# 3_DAC.net
KiCad netlist of a schematic drawn in Altium Designer
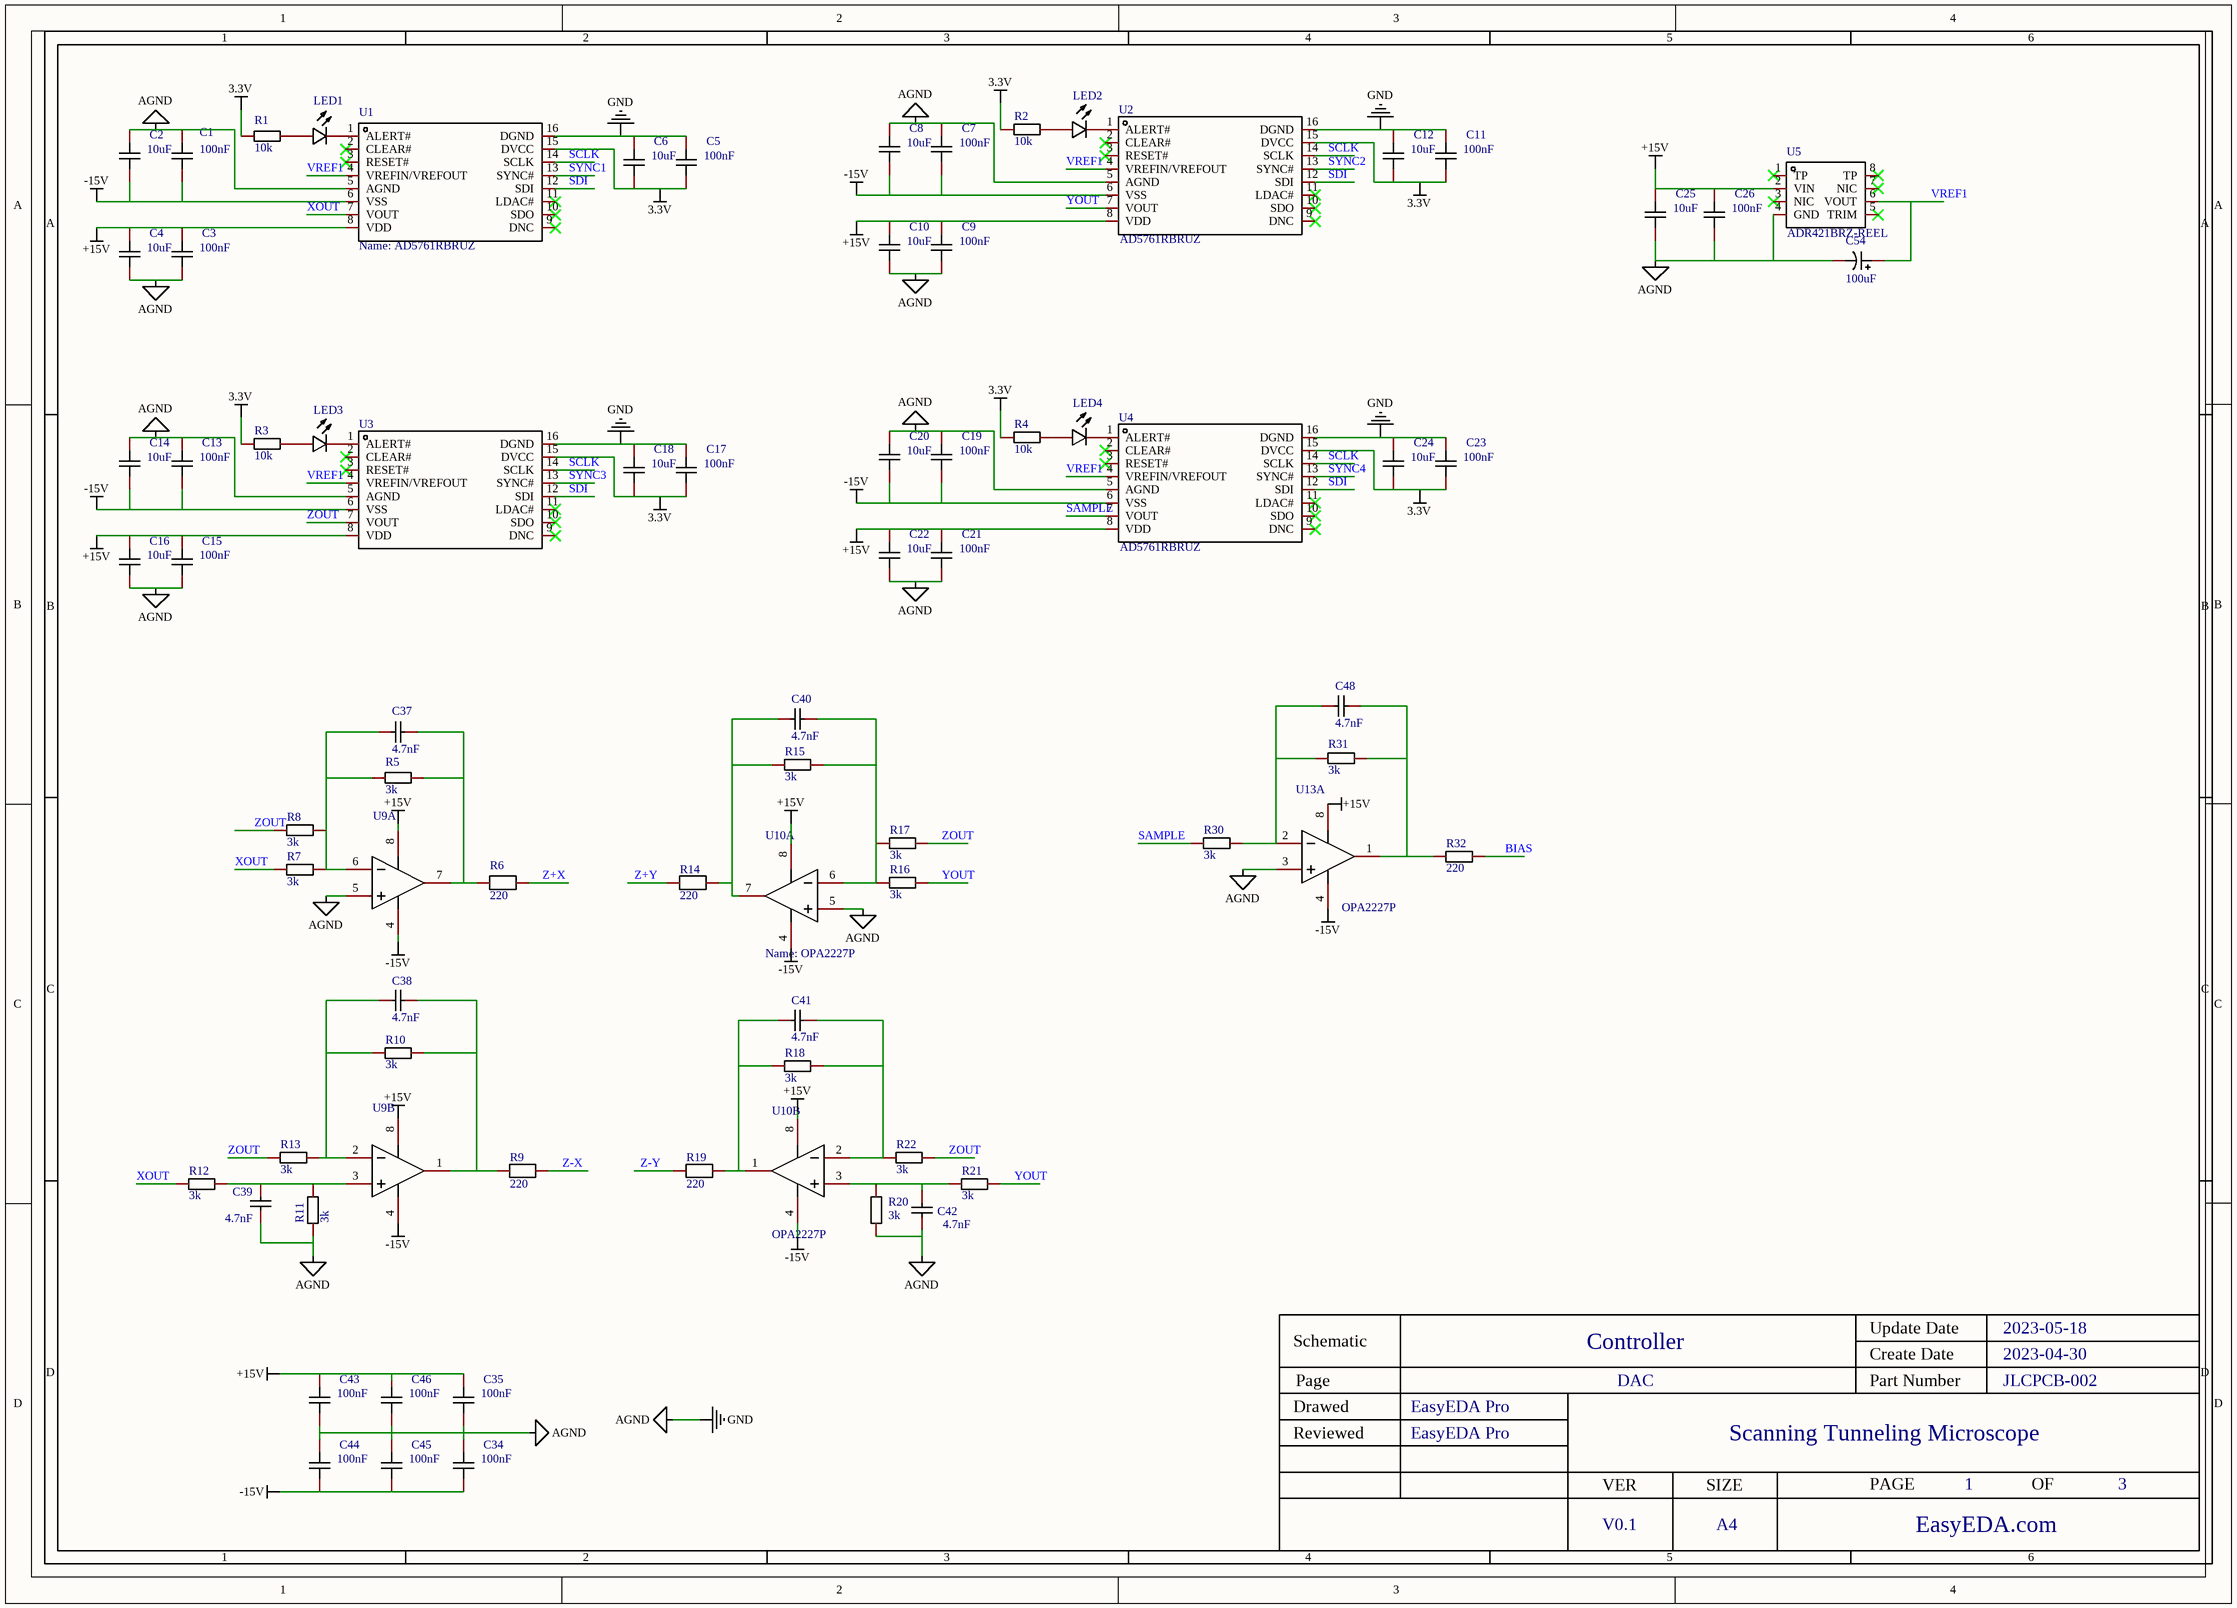
[diagram p0: 3_DAC.schdoc]

(export (version "E")
  (design (tool "Eeschema 10.0.6"))
  (components
    (comp (ref "C1")
      (value "100nF")
      (description "容值:100nF;精度:±10%;额定电压:25V;温度系数:X7R;")
      (fields
        (field (name "MANUFACTURER") "SAMSUNG(三星)")
        (field (name "MANUFACTURER PART") "CL10B104KA8NNNC")
      )
      (libsource (lib "altium-import") (part "root_1_CL10B104KA8NNNC_"))
    )
    (comp (ref "C2")
      (value "10uF")
      (description "容值:10uF;精度:±20%;额定电压:25V;温度系数:X5R;")
      (fields
        (field (name "MANUFACTURER") "muRata(村田)")
        (field (name "MANUFACTURER PART") "GRM188R61E106MA73D")
      )
      (libsource (lib "altium-import") (part "root_1_GRM188R61E106MA73D_"))
    )
    (comp (ref "C3")
      (value "100nF")
      (description "容值:100nF;精度:±10%;额定电压:25V;温度系数:X7R;")
      (fields
        (field (name "MANUFACTURER") "SAMSUNG(三星)")
        (field (name "MANUFACTURER PART") "CL10B104KA8NNNC")
      )
      (libsource (lib "altium-import") (part "root_1_CL10B104KA8NNNC_"))
    )
    (comp (ref "C4")
      (value "10uF")
      (description "容值:10uF;精度:±20%;额定电压:25V;温度系数:X5R;")
      (fields
        (field (name "MANUFACTURER") "muRata(村田)")
        (field (name "MANUFACTURER PART") "GRM188R61E106MA73D")
      )
      (libsource (lib "altium-import") (part "root_1_GRM188R61E106MA73D_"))
    )
    (comp (ref "C5")
      (value "100nF")
      (description "容值:100nF;精度:±10%;额定电压:25V;温度系数:X7R;")
      (fields
        (field (name "MANUFACTURER") "SAMSUNG(三星)")
        (field (name "MANUFACTURER PART") "CL10B104KA8NNNC")
      )
      (libsource (lib "altium-import") (part "root_1_CL10B104KA8NNNC_"))
    )
    (comp (ref "C6")
      (value "10uF")
      (description "容值:10uF;精度:±20%;额定电压:25V;温度系数:X5R;")
      (fields
        (field (name "MANUFACTURER") "muRata(村田)")
        (field (name "MANUFACTURER PART") "GRM188R61E106MA73D")
      )
      (libsource (lib "altium-import") (part "root_1_GRM188R61E106MA73D_"))
    )
    (comp (ref "C7")
      (value "100nF")
      (description "容值:100nF;精度:±10%;额定电压:25V;温度系数:X7R;")
      (fields
        (field (name "MANUFACTURER") "SAMSUNG(三星)")
        (field (name "MANUFACTURER PART") "CL10B104KA8NNNC")
      )
      (libsource (lib "altium-import") (part "root_1_CL10B104KA8NNNC_"))
    )
    (comp (ref "C8")
      (value "10uF")
      (description "容值:10uF;精度:±20%;额定电压:25V;温度系数:X5R;")
      (fields
        (field (name "MANUFACTURER") "muRata(村田)")
        (field (name "MANUFACTURER PART") "GRM188R61E106MA73D")
      )
      (libsource (lib "altium-import") (part "root_1_GRM188R61E106MA73D_"))
    )
    (comp (ref "C9")
      (value "100nF")
      (description "容值:100nF;精度:±10%;额定电压:25V;温度系数:X7R;")
      (fields
        (field (name "MANUFACTURER") "SAMSUNG(三星)")
        (field (name "MANUFACTURER PART") "CL10B104KA8NNNC")
      )
      (libsource (lib "altium-import") (part "root_1_CL10B104KA8NNNC_"))
    )
    (comp (ref "C10")
      (value "10uF")
      (description "容值:10uF;精度:±20%;额定电压:25V;温度系数:X5R;")
      (fields
        (field (name "MANUFACTURER") "muRata(村田)")
        (field (name "MANUFACTURER PART") "GRM188R61E106MA73D")
      )
      (libsource (lib "altium-import") (part "root_1_GRM188R61E106MA73D_"))
    )
    (comp (ref "C11")
      (value "100nF")
      (description "容值:100nF;精度:±10%;额定电压:25V;温度系数:X7R;")
      (fields
        (field (name "MANUFACTURER") "SAMSUNG(三星)")
        (field (name "MANUFACTURER PART") "CL10B104KA8NNNC")
      )
      (libsource (lib "altium-import") (part "root_1_CL10B104KA8NNNC_"))
    )
    (comp (ref "C12")
      (value "10uF")
      (description "容值:10uF;精度:±20%;额定电压:25V;温度系数:X5R;")
      (fields
        (field (name "MANUFACTURER") "muRata(村田)")
        (field (name "MANUFACTURER PART") "GRM188R61E106MA73D")
      )
      (libsource (lib "altium-import") (part "root_1_GRM188R61E106MA73D_"))
    )
    (comp (ref "C13")
      (value "100nF")
      (description "容值:100nF;精度:±10%;额定电压:25V;温度系数:X7R;")
      (fields
        (field (name "MANUFACTURER") "SAMSUNG(三星)")
        (field (name "MANUFACTURER PART") "CL10B104KA8NNNC")
      )
      (libsource (lib "altium-import") (part "root_1_CL10B104KA8NNNC_"))
    )
    (comp (ref "C14")
      (value "10uF")
      (description "容值:10uF;精度:±20%;额定电压:25V;温度系数:X5R;")
      (fields
        (field (name "MANUFACTURER") "muRata(村田)")
        (field (name "MANUFACTURER PART") "GRM188R61E106MA73D")
      )
      (libsource (lib "altium-import") (part "root_1_GRM188R61E106MA73D_"))
    )
    (comp (ref "C15")
      (value "100nF")
      (description "容值:100nF;精度:±10%;额定电压:25V;温度系数:X7R;")
      (fields
        (field (name "MANUFACTURER") "SAMSUNG(三星)")
        (field (name "MANUFACTURER PART") "CL10B104KA8NNNC")
      )
      (libsource (lib "altium-import") (part "root_1_CL10B104KA8NNNC_"))
    )
    (comp (ref "C16")
      (value "10uF")
      (description "容值:10uF;精度:±20%;额定电压:25V;温度系数:X5R;")
      (fields
        (field (name "MANUFACTURER") "muRata(村田)")
        (field (name "MANUFACTURER PART") "GRM188R61E106MA73D")
      )
      (libsource (lib "altium-import") (part "root_1_GRM188R61E106MA73D_"))
    )
    (comp (ref "C17")
      (value "100nF")
      (description "容值:100nF;精度:±10%;额定电压:25V;温度系数:X7R;")
      (fields
        (field (name "MANUFACTURER") "SAMSUNG(三星)")
        (field (name "MANUFACTURER PART") "CL10B104KA8NNNC")
      )
      (libsource (lib "altium-import") (part "root_1_CL10B104KA8NNNC_"))
    )
    (comp (ref "C18")
      (value "10uF")
      (description "容值:10uF;精度:±20%;额定电压:25V;温度系数:X5R;")
      (fields
        (field (name "MANUFACTURER") "muRata(村田)")
        (field (name "MANUFACTURER PART") "GRM188R61E106MA73D")
      )
      (libsource (lib "altium-import") (part "root_1_GRM188R61E106MA73D_"))
    )
    (comp (ref "C19")
      (value "100nF")
      (description "容值:100nF;精度:±10%;额定电压:25V;温度系数:X7R;")
      (fields
        (field (name "MANUFACTURER") "SAMSUNG(三星)")
        (field (name "MANUFACTURER PART") "CL10B104KA8NNNC")
      )
      (libsource (lib "altium-import") (part "root_1_CL10B104KA8NNNC_"))
    )
    (comp (ref "C20")
      (value "10uF")
      (description "容值:10uF;精度:±20%;额定电压:25V;温度系数:X5R;")
      (fields
        (field (name "MANUFACTURER") "muRata(村田)")
        (field (name "MANUFACTURER PART") "GRM188R61E106MA73D")
      )
      (libsource (lib "altium-import") (part "root_1_GRM188R61E106MA73D_"))
    )
    (comp (ref "C21")
      (value "100nF")
      (description "容值:100nF;精度:±10%;额定电压:25V;温度系数:X7R;")
      (fields
        (field (name "MANUFACTURER") "SAMSUNG(三星)")
        (field (name "MANUFACTURER PART") "CL10B104KA8NNNC")
      )
      (libsource (lib "altium-import") (part "root_1_CL10B104KA8NNNC_"))
    )
    (comp (ref "C22")
      (value "10uF")
      (description "容值:10uF;精度:±20%;额定电压:25V;温度系数:X5R;")
      (fields
        (field (name "MANUFACTURER") "muRata(村田)")
        (field (name "MANUFACTURER PART") "GRM188R61E106MA73D")
      )
      (libsource (lib "altium-import") (part "root_1_GRM188R61E106MA73D_"))
    )
    (comp (ref "C23")
      (value "100nF")
      (description "容值:100nF;精度:±10%;额定电压:25V;温度系数:X7R;")
      (fields
        (field (name "MANUFACTURER") "SAMSUNG(三星)")
        (field (name "MANUFACTURER PART") "CL10B104KA8NNNC")
      )
      (libsource (lib "altium-import") (part "root_1_CL10B104KA8NNNC_"))
    )
    (comp (ref "C24")
      (value "10uF")
      (description "容值:10uF;精度:±20%;额定电压:25V;温度系数:X5R;")
      (fields
        (field (name "MANUFACTURER") "muRata(村田)")
        (field (name "MANUFACTURER PART") "GRM188R61E106MA73D")
      )
      (libsource (lib "altium-import") (part "root_1_GRM188R61E106MA73D_"))
    )
    (comp (ref "C25")
      (value "10uF")
      (description "容值:10uF;精度:±20%;额定电压:25V;温度系数:X5R;")
      (fields
        (field (name "MANUFACTURER") "muRata(村田)")
        (field (name "MANUFACTURER PART") "GRM188R61E106MA73D")
      )
      (libsource (lib "altium-import") (part "root_1_GRM188R61E106MA73D_"))
    )
    (comp (ref "C26")
      (value "100nF")
      (description "容值:100nF;精度:±10%;额定电压:25V;温度系数:X7R;")
      (fields
        (field (name "MANUFACTURER") "SAMSUNG(三星)")
        (field (name "MANUFACTURER PART") "CL10B104KA8NNNC")
      )
      (libsource (lib "altium-import") (part "root_1_CL10B104KA8NNNC_"))
    )
    (comp (ref "C34")
      (value "100nF")
      (description "容值:100nF;精度:±10%;额定电压:25V;温度系数:X7R;")
      (fields
        (field (name "MANUFACTURER") "SAMSUNG(三星)")
        (field (name "MANUFACTURER PART") "CL10B104KA8NNNC")
      )
      (libsource (lib "altium-import") (part "root_1_CL10B104KA8NNNC_"))
    )
    (comp (ref "C35")
      (value "100nF")
      (description "容值:100nF;精度:±10%;额定电压:25V;温度系数:X7R;")
      (fields
        (field (name "MANUFACTURER") "SAMSUNG(三星)")
        (field (name "MANUFACTURER PART") "CL10B104KA8NNNC")
      )
      (libsource (lib "altium-import") (part "root_1_CL10B104KA8NNNC_"))
    )
    (comp (ref "C37")
      (value "4.7nF")
      (description "容值:4.7nF;精度:±10%;额定电压:50V;温度系数:X7R;")
      (fields (field (name "MANUFACTURER") "FH(风华)") (field (name "MANUFACTURER PART") "0603B472K500NT"))
      (libsource (lib "altium-import") (part "root_0_0603B472K500NT_"))
    )
    (comp (ref "C38")
      (value "4.7nF")
      (description "容值:4.7nF;精度:±10%;额定电压:50V;温度系数:X7R;")
      (fields (field (name "MANUFACTURER") "FH(风华)") (field (name "MANUFACTURER PART") "0603B472K500NT"))
      (libsource (lib "altium-import") (part "root_0_0603B472K500NT_"))
    )
    (comp (ref "C39")
      (value "4.7nF")
      (description "容值:4.7nF;精度:±10%;额定电压:50V;温度系数:X7R;")
      (fields (field (name "MANUFACTURER") "FH(风华)") (field (name "MANUFACTURER PART") "0603B472K500NT"))
      (libsource (lib "altium-import") (part "root_1_0603B472K500NT_"))
    )
    (comp (ref "C40")
      (value "4.7nF")
      (description "容值:4.7nF;精度:±10%;额定电压:50V;温度系数:X7R;")
      (fields (field (name "MANUFACTURER") "FH(风华)") (field (name "MANUFACTURER PART") "0603B472K500NT"))
      (libsource (lib "altium-import") (part "root_0_0603B472K500NT_"))
    )
    (comp (ref "C41")
      (value "4.7nF")
      (description "容值:4.7nF;精度:±10%;额定电压:50V;温度系数:X7R;")
      (fields (field (name "MANUFACTURER") "FH(风华)") (field (name "MANUFACTURER PART") "0603B472K500NT"))
      (libsource (lib "altium-import") (part "root_0_0603B472K500NT_"))
    )
    (comp (ref "C42")
      (value "4.7nF")
      (description "容值:4.7nF;精度:±10%;额定电压:50V;温度系数:X7R;")
      (fields (field (name "MANUFACTURER") "FH(风华)") (field (name "MANUFACTURER PART") "0603B472K500NT"))
      (libsource (lib "altium-import") (part "root_3_0603B472K500NT_"))
    )
    (comp (ref "C43")
      (value "100nF")
      (description "容值:100nF;精度:±10%;额定电压:25V;温度系数:X7R;")
      (fields
        (field (name "MANUFACTURER") "SAMSUNG(三星)")
        (field (name "MANUFACTURER PART") "CL10B104KA8NNNC")
      )
      (libsource (lib "altium-import") (part "root_1_CL10B104KA8NNNC_"))
    )
    (comp (ref "C44")
      (value "100nF")
      (description "容值:100nF;精度:±10%;额定电压:25V;温度系数:X7R;")
      (fields
        (field (name "MANUFACTURER") "SAMSUNG(三星)")
        (field (name "MANUFACTURER PART") "CL10B104KA8NNNC")
      )
      (libsource (lib "altium-import") (part "root_1_CL10B104KA8NNNC_"))
    )
    (comp (ref "C45")
      (value "100nF")
      (description "容值:100nF;精度:±10%;额定电压:25V;温度系数:X7R;")
      (fields
        (field (name "MANUFACTURER") "SAMSUNG(三星)")
        (field (name "MANUFACTURER PART") "CL10B104KA8NNNC")
      )
      (libsource (lib "altium-import") (part "root_1_CL10B104KA8NNNC_"))
    )
    (comp (ref "C46")
      (value "100nF")
      (description "容值:100nF;精度:±10%;额定电压:25V;温度系数:X7R;")
      (fields
        (field (name "MANUFACTURER") "SAMSUNG(三星)")
        (field (name "MANUFACTURER PART") "CL10B104KA8NNNC")
      )
      (libsource (lib "altium-import") (part "root_1_CL10B104KA8NNNC_"))
    )
    (comp (ref "C48")
      (value "4.7nF")
      (description "容值:4.7nF;精度:±10%;额定电压:50V;温度系数:X7R;")
      (fields (field (name "MANUFACTURER") "FH(风华)") (field (name "MANUFACTURER PART") "0603B472K500NT"))
      (libsource (lib "altium-import") (part "root_0_0603B472K500NT_"))
    )
    (comp (ref "C54")
      (value "100uF")
      (fields
        (field (name "NAME") "100uF")
        (field (name "MANUFACTURER") "Kyocera AVX")
        (field (name "MANUFACTURER PART") "F931D107MNC")
        (field (name "TOLERANCE") "±20%")
      )
      (libsource (lib "altium-import") (part "root_2_F931D107MNC_"))
    )
    (comp (ref "LED1")
      (value "19-217/R6C-AL1M2VY/3T")
      (fields (field (name "MANUFACTURER") "EVERLIGHT(台湾亿光)"))
      (libsource (lib "altium-import") (part "root_0_19-217/R6C-AL1M2VY/3T_"))
    )
    (comp (ref "LED2")
      (value "19-217/R6C-AL1M2VY/3T")
      (fields (field (name "MANUFACTURER") "EVERLIGHT(台湾亿光)"))
      (libsource (lib "altium-import") (part "root_0_19-217/R6C-AL1M2VY/3T_"))
    )
    (comp (ref "LED3")
      (value "19-217/R6C-AL1M2VY/3T")
      (fields (field (name "MANUFACTURER") "EVERLIGHT(台湾亿光)"))
      (libsource (lib "altium-import") (part "root_0_19-217/R6C-AL1M2VY/3T_"))
    )
    (comp (ref "LED4")
      (value "19-217/R6C-AL1M2VY/3T")
      (fields (field (name "MANUFACTURER") "EVERLIGHT(台湾亿光)"))
      (libsource (lib "altium-import") (part "root_0_19-217/R6C-AL1M2VY/3T_"))
    )
    (comp (ref "R1")
      (value "10k")
      (description "电阻类型:厚膜电阻;阻值:10k;精度:±1%;功率:1/10W;温度系数:±100ppm/;最大工作电压:75V;工作温度范围:-55~+155;")
      (fields
        (field (name "MANUFACTURER") "UNI-ROYAL(厚声)")
        (field (name "MANUFACTURER PART") "0603WAF1002T5E")
      )
      (libsource (lib "altium-import") (part "root_0_0603WAF1002T5E_"))
    )
    (comp (ref "R2")
      (value "10k")
      (description "电阻类型:厚膜电阻;阻值:10k;精度:±1%;功率:1/10W;温度系数:±100ppm/;最大工作电压:75V;工作温度范围:-55~+155;")
      (fields
        (field (name "MANUFACTURER") "UNI-ROYAL(厚声)")
        (field (name "MANUFACTURER PART") "0603WAF1002T5E")
      )
      (libsource (lib "altium-import") (part "root_0_0603WAF1002T5E_"))
    )
    (comp (ref "R3")
      (value "10k")
      (description "电阻类型:厚膜电阻;阻值:10k;精度:±1%;功率:1/10W;温度系数:±100ppm/;最大工作电压:75V;工作温度范围:-55~+155;")
      (fields
        (field (name "MANUFACTURER") "UNI-ROYAL(厚声)")
        (field (name "MANUFACTURER PART") "0603WAF1002T5E")
      )
      (libsource (lib "altium-import") (part "root_0_0603WAF1002T5E_"))
    )
    (comp (ref "R4")
      (value "10k")
      (description "电阻类型:厚膜电阻;阻值:10k;精度:±1%;功率:1/10W;温度系数:±100ppm/;最大工作电压:75V;工作温度范围:-55~+155;")
      (fields
        (field (name "MANUFACTURER") "UNI-ROYAL(厚声)")
        (field (name "MANUFACTURER PART") "0603WAF1002T5E")
      )
      (libsource (lib "altium-import") (part "root_0_0603WAF1002T5E_"))
    )
    (comp (ref "R5")
      (value "3k")
      (description "电阻类型:薄膜电阻;阻值:3k;精度:±0.5%;功率:100mW;温度系数:±25ppm/;最大工作电压:75V;工作温度范围:-55~+155;")
      (fields (field (name "MANUFACTURER") "光颉(Viking)") (field (name "MANUFACTURER PART") "ARG03DTC3001"))
      (libsource (lib "altium-import") (part "root_0_ARG03DTC3001_"))
    )
    (comp (ref "R6")
      (value "220")
      (description "阻值:220;精度:±0.5%;功率:100mW;温度系数:±50ppm/;最大工作电压:-;工作温度范围:-55~+155;")
      (fields (field (name "MANUFACTURER") "PANASONIC(松下)") (field (name "MANUFACTURER PART") "ERJU3RD2200V"))
      (libsource (lib "altium-import") (part "root_0_ERJU3RD2200V_"))
    )
    (comp (ref "R7")
      (value "3k")
      (description "电阻类型:薄膜电阻;阻值:3k;精度:±0.5%;功率:100mW;温度系数:±25ppm/;最大工作电压:75V;工作温度范围:-55~+155;")
      (fields (field (name "MANUFACTURER") "光颉(Viking)") (field (name "MANUFACTURER PART") "ARG03DTC3001"))
      (libsource (lib "altium-import") (part "root_0_ARG03DTC3001_"))
    )
    (comp (ref "R8")
      (value "3k")
      (description "电阻类型:薄膜电阻;阻值:3k;精度:±0.5%;功率:100mW;温度系数:±25ppm/;最大工作电压:75V;工作温度范围:-55~+155;")
      (fields (field (name "MANUFACTURER") "光颉(Viking)") (field (name "MANUFACTURER PART") "ARG03DTC3001"))
      (libsource (lib "altium-import") (part "root_0_ARG03DTC3001_"))
    )
    (comp (ref "R9")
      (value "220")
      (description "阻值:220;精度:±0.5%;功率:100mW;温度系数:±50ppm/;最大工作电压:-;工作温度范围:-55~+155;")
      (fields (field (name "MANUFACTURER") "PANASONIC(松下)") (field (name "MANUFACTURER PART") "ERJU3RD2200V"))
      (libsource (lib "altium-import") (part "root_0_ERJU3RD2200V_"))
    )
    (comp (ref "R10")
      (value "3k")
      (description "电阻类型:薄膜电阻;阻值:3k;精度:±0.5%;功率:100mW;温度系数:±25ppm/;最大工作电压:75V;工作温度范围:-55~+155;")
      (fields (field (name "MANUFACTURER") "光颉(Viking)") (field (name "MANUFACTURER PART") "ARG03DTC3001"))
      (libsource (lib "altium-import") (part "root_0_ARG03DTC3001_"))
    )
    (comp (ref "R11")
      (value "3k")
      (description "电阻类型:薄膜电阻;阻值:3k;精度:±0.5%;功率:100mW;温度系数:±25ppm/;最大工作电压:75V;工作温度范围:-55~+155;")
      (fields (field (name "MANUFACTURER") "光颉(Viking)") (field (name "MANUFACTURER PART") "ARG03DTC3001"))
      (libsource (lib "altium-import") (part "root_1_ARG03DTC3001_"))
    )
    (comp (ref "R12")
      (value "3k")
      (description "电阻类型:薄膜电阻;阻值:3k;精度:±0.5%;功率:100mW;温度系数:±25ppm/;最大工作电压:75V;工作温度范围:-55~+155;")
      (fields (field (name "MANUFACTURER") "光颉(Viking)") (field (name "MANUFACTURER PART") "ARG03DTC3001"))
      (libsource (lib "altium-import") (part "root_0_ARG03DTC3001_"))
    )
    (comp (ref "R13")
      (value "3k")
      (description "电阻类型:薄膜电阻;阻值:3k;精度:±0.5%;功率:100mW;温度系数:±25ppm/;最大工作电压:75V;工作温度范围:-55~+155;")
      (fields (field (name "MANUFACTURER") "光颉(Viking)") (field (name "MANUFACTURER PART") "ARG03DTC3001"))
      (libsource (lib "altium-import") (part "root_0_ARG03DTC3001_"))
    )
    (comp (ref "R14")
      (value "220")
      (description "阻值:220;精度:±0.5%;功率:100mW;温度系数:±50ppm/;最大工作电压:-;工作温度范围:-55~+155;")
      (fields (field (name "MANUFACTURER") "PANASONIC(松下)") (field (name "MANUFACTURER PART") "ERJU3RD2200V"))
      (libsource (lib "altium-import") (part "root_0_ERJU3RD2200V_"))
    )
    (comp (ref "R15")
      (value "3k")
      (description "电阻类型:薄膜电阻;阻值:3k;精度:±0.5%;功率:100mW;温度系数:±25ppm/;最大工作电压:75V;工作温度范围:-55~+155;")
      (fields (field (name "MANUFACTURER") "光颉(Viking)") (field (name "MANUFACTURER PART") "ARG03DTC3001"))
      (libsource (lib "altium-import") (part "root_0_ARG03DTC3001_"))
    )
    (comp (ref "R16")
      (value "3k")
      (description "电阻类型:薄膜电阻;阻值:3k;精度:±0.5%;功率:100mW;温度系数:±25ppm/;最大工作电压:75V;工作温度范围:-55~+155;")
      (fields (field (name "MANUFACTURER") "光颉(Viking)") (field (name "MANUFACTURER PART") "ARG03DTC3001"))
      (libsource (lib "altium-import") (part "root_0_ARG03DTC3001_"))
    )
    (comp (ref "R17")
      (value "3k")
      (description "电阻类型:薄膜电阻;阻值:3k;精度:±0.5%;功率:100mW;温度系数:±25ppm/;最大工作电压:75V;工作温度范围:-55~+155;")
      (fields (field (name "MANUFACTURER") "光颉(Viking)") (field (name "MANUFACTURER PART") "ARG03DTC3001"))
      (libsource (lib "altium-import") (part "root_0_ARG03DTC3001_"))
    )
    (comp (ref "R18")
      (value "3k")
      (description "电阻类型:薄膜电阻;阻值:3k;精度:±0.5%;功率:100mW;温度系数:±25ppm/;最大工作电压:75V;工作温度范围:-55~+155;")
      (fields (field (name "MANUFACTURER") "光颉(Viking)") (field (name "MANUFACTURER PART") "ARG03DTC3001"))
      (libsource (lib "altium-import") (part "root_0_ARG03DTC3001_"))
    )
    (comp (ref "R19")
      (value "220")
      (description "阻值:220;精度:±0.5%;功率:100mW;温度系数:±50ppm/;最大工作电压:-;工作温度范围:-55~+155;")
      (fields (field (name "MANUFACTURER") "PANASONIC(松下)") (field (name "MANUFACTURER PART") "ERJU3RD2200V"))
      (libsource (lib "altium-import") (part "root_0_ERJU3RD2200V_"))
    )
    (comp (ref "R20")
      (value "3k")
      (description "电阻类型:薄膜电阻;阻值:3k;精度:±0.5%;功率:100mW;温度系数:±25ppm/;最大工作电压:75V;工作温度范围:-55~+155;")
      (fields (field (name "MANUFACTURER") "光颉(Viking)") (field (name "MANUFACTURER PART") "ARG03DTC3001"))
      (libsource (lib "altium-import") (part "root_3_ARG03DTC3001_"))
    )
    (comp (ref "R21")
      (value "3k")
      (description "电阻类型:薄膜电阻;阻值:3k;精度:±0.5%;功率:100mW;温度系数:±25ppm/;最大工作电压:75V;工作温度范围:-55~+155;")
      (fields (field (name "MANUFACTURER") "光颉(Viking)") (field (name "MANUFACTURER PART") "ARG03DTC3001"))
      (libsource (lib "altium-import") (part "root_0_ARG03DTC3001_"))
    )
    (comp (ref "R22")
      (value "3k")
      (description "电阻类型:薄膜电阻;阻值:3k;精度:±0.5%;功率:100mW;温度系数:±25ppm/;最大工作电压:75V;工作温度范围:-55~+155;")
      (fields (field (name "MANUFACTURER") "光颉(Viking)") (field (name "MANUFACTURER PART") "ARG03DTC3001"))
      (libsource (lib "altium-import") (part "root_0_ARG03DTC3001_"))
    )
    (comp (ref "R30")
      (value "3k")
      (description "电阻类型:薄膜电阻;阻值:3k;精度:±0.5%;功率:100mW;温度系数:±25ppm/;最大工作电压:75V;工作温度范围:-55~+155;")
      (fields (field (name "MANUFACTURER") "光颉(Viking)") (field (name "MANUFACTURER PART") "ARG03DTC3001"))
      (libsource (lib "altium-import") (part "root_0_ARG03DTC3001_"))
    )
    (comp (ref "R31")
      (value "3k")
      (description "电阻类型:薄膜电阻;阻值:3k;精度:±0.5%;功率:100mW;温度系数:±25ppm/;最大工作电压:75V;工作温度范围:-55~+155;")
      (fields (field (name "MANUFACTURER") "光颉(Viking)") (field (name "MANUFACTURER PART") "ARG03DTC3001"))
      (libsource (lib "altium-import") (part "root_0_ARG03DTC3001_"))
    )
    (comp (ref "R32")
      (value "220")
      (description "电阻类型:薄膜电阻;阻值:3k;精度:±0.5%;功率:100mW;温度系数:±25ppm/;最大工作电压:75V;工作温度范围:-55~+155;")
      (fields (field (name "MANUFACTURER") "光颉(Viking)") (field (name "MANUFACTURER PART") "ARG03DTC3001"))
      (libsource (lib "altium-import") (part "root_0_ARG03DTC3001_"))
    )
    (comp (ref "U1")
      (value "AD5761RBRUZ")
      (description "D/A 位数:-;D/A通道数:-;输出类型:-;读写接口类型:-;")
      (fields (field (name "NAME") "AD5761RBRUZ") (field (name "MANUFACTURER") "ADI(亚德诺)/LINEAR"))
      (libsource (lib "altium-import") (part "root_0_AD5761RBRUZ_"))
    )
    (comp (ref "U2")
      (value "AD5761RBRUZ")
      (description "D/A 位数:-;D/A通道数:-;输出类型:-;读写接口类型:-;")
      (fields (field (name "NAME") "AD5761RBRUZ") (field (name "MANUFACTURER") "ADI(亚德诺)/LINEAR"))
      (libsource (lib "altium-import") (part "root_0_AD5761RBRUZ_"))
    )
    (comp (ref "U3")
      (value "AD5761RBRUZ")
      (description "D/A 位数:-;D/A通道数:-;输出类型:-;读写接口类型:-;")
      (fields (field (name "MANUFACTURER") "ADI(亚德诺)/LINEAR"))
      (libsource (lib "altium-import") (part "root_0_AD5761RBRUZ_"))
    )
    (comp (ref "U4")
      (value "AD5761RBRUZ")
      (description "D/A 位数:-;D/A通道数:-;输出类型:-;读写接口类型:-;")
      (fields (field (name "NAME") "AD5761RBRUZ") (field (name "MANUFACTURER") "ADI(亚德诺)/LINEAR"))
      (libsource (lib "altium-import") (part "root_0_AD5761RBRUZ_"))
    )
    (comp (ref "U5")
      (value "ADR421BRZ-REEL")
      (fields (field (name "NAME") "ADR421BRZ-REEL") (field (name "MANUFACTURER") "ADI(亚德诺)/LINEAR"))
      (libsource (lib "altium-import") (part "root_0_ADR421BRZ-REEL_"))
    )
    (comp (ref "U9")
      (value "OPA2227P")
      (fields (field (name "MANUFACTURER") "TI(德州仪器)"))
      (libsource (lib "altium-import") (part "root_0_OPA2227P_"))
    )
    (comp (ref "U10")
      (value "OPA2227P")
      (fields (field (name "NAME") "OPA2227P") (field (name "MANUFACTURER") "TI(德州仪器)"))
      (libsource (lib "altium-import") (part "root_0_mirrored_OPA2227P_"))
    )
    (comp (ref "U13")
      (value "OPA2227P")
      (fields (field (name "NAME") "OPA2227P") (field (name "MANUFACTURER") "TI(德州仪器)"))
      (libsource (lib "") (part "root_0_OPA2227P__1"))
    )
  )
  (nets
    (net (code "1") (name "+15V") (class "Default")
      (node (ref "C10") (pin "2") (pinfunction "2_2") (pintype "passive"))
      (node (ref "C15") (pin "2") (pinfunction "2_2") (pintype "passive"))
      (node (ref "C16") (pin "2") (pinfunction "2_2") (pintype "passive"))
      (node (ref "C21") (pin "2") (pinfunction "2_2") (pintype "passive"))
      (node (ref "C22") (pin "2") (pinfunction "2_2") (pintype "passive"))
      (node (ref "C25") (pin "2") (pinfunction "2_2") (pintype "passive"))
      (node (ref "C26") (pin "2") (pinfunction "2_2") (pintype "passive"))
      (node (ref "C3") (pin "2") (pinfunction "2_2") (pintype "passive"))
      (node (ref "C35") (pin "2") (pinfunction "2_2") (pintype "passive"))
      (node (ref "C4") (pin "2") (pinfunction "2_2") (pintype "passive"))
      (node (ref "C43") (pin "2") (pinfunction "2_2") (pintype "passive"))
      (node (ref "C46") (pin "2") (pinfunction "2_2") (pintype "passive"))
      (node (ref "C9") (pin "2") (pinfunction "2_2") (pintype "passive"))
      (node (ref "U1") (pin "8") (pinfunction "VDD_8") (pintype "passive"))
      (node (ref "U10") (pin "8") (pinfunction "V+_8") (pintype "passive"))
      (node (ref "U13") (pin "8") (pinfunction "V+_8") (pintype "passive"))
      (node (ref "U2") (pin "8") (pinfunction "VDD_8") (pintype "passive"))
      (node (ref "U3") (pin "8") (pinfunction "VDD_8") (pintype "passive"))
      (node (ref "U4") (pin "8") (pinfunction "VDD_8") (pintype "passive"))
      (node (ref "U5") (pin "2") (pinfunction "VIN_2") (pintype "passive"))
      (node (ref "U9") (pin "8") (pinfunction "V+_8") (pintype "passive"))
    )
    (net (code "2") (name "-15V") (class "Default")
      (node (ref "C1") (pin "1") (pinfunction "1_1") (pintype "passive"))
      (node (ref "C13") (pin "1") (pinfunction "1_1") (pintype "passive"))
      (node (ref "C14") (pin "1") (pinfunction "1_1") (pintype "passive"))
      (node (ref "C19") (pin "1") (pinfunction "1_1") (pintype "passive"))
      (node (ref "C2") (pin "1") (pinfunction "1_1") (pintype "passive"))
      (node (ref "C20") (pin "1") (pinfunction "1_1") (pintype "passive"))
      (node (ref "C34") (pin "1") (pinfunction "1_1") (pintype "passive"))
      (node (ref "C44") (pin "1") (pinfunction "1_1") (pintype "passive"))
      (node (ref "C45") (pin "1") (pinfunction "1_1") (pintype "passive"))
      (node (ref "C7") (pin "1") (pinfunction "1_1") (pintype "passive"))
      (node (ref "C8") (pin "1") (pinfunction "1_1") (pintype "passive"))
      (node (ref "U1") (pin "6") (pinfunction "VSS_6") (pintype "passive"))
      (node (ref "U10") (pin "4") (pinfunction "V-_4") (pintype "passive"))
      (node (ref "U13") (pin "4") (pinfunction "V-_4") (pintype "passive"))
      (node (ref "U2") (pin "6") (pinfunction "VSS_6") (pintype "passive"))
      (node (ref "U3") (pin "6") (pinfunction "VSS_6") (pintype "passive"))
      (node (ref "U4") (pin "6") (pinfunction "VSS_6") (pintype "passive"))
      (node (ref "U9") (pin "4") (pinfunction "V-_4") (pintype "passive"))
    )
    (net (code "3") (name "/BIAS") (class "Default")
      (node (ref "R32") (pin "2") (pinfunction "2_2") (pintype "passive"))
    )
    (net (code "4") (name "/SAMPLE") (class "Default")
      (node (ref "R30") (pin "1") (pinfunction "1_1") (pintype "passive"))
      (node (ref "U4") (pin "7") (pinfunction "VOUT_7") (pintype "passive"))
    )
    (net (code "5") (name "/SCLK") (class "Default")
      (node (ref "U1") (pin "14") (pinfunction "SCLK_14") (pintype "passive"))
      (node (ref "U2") (pin "14") (pinfunction "SCLK_14") (pintype "passive"))
      (node (ref "U3") (pin "14") (pinfunction "SCLK_14") (pintype "passive"))
      (node (ref "U4") (pin "14") (pinfunction "SCLK_14") (pintype "passive"))
    )
    (net (code "6") (name "/SDI") (class "Default")
      (node (ref "U1") (pin "12") (pinfunction "SDI_12") (pintype "passive"))
      (node (ref "U2") (pin "12") (pinfunction "SDI_12") (pintype "passive"))
      (node (ref "U3") (pin "12") (pinfunction "SDI_12") (pintype "passive"))
      (node (ref "U4") (pin "12") (pinfunction "SDI_12") (pintype "passive"))
    )
    (net (code "7") (name "/SYNC1") (class "Default")
      (node (ref "U1") (pin "13") (pinfunction "SYNC#_13") (pintype "passive"))
    )
    (net (code "8") (name "/SYNC2") (class "Default")
      (node (ref "U2") (pin "13") (pinfunction "SYNC#_13") (pintype "passive"))
    )
    (net (code "9") (name "/SYNC3") (class "Default")
      (node (ref "U3") (pin "13") (pinfunction "SYNC#_13") (pintype "passive"))
    )
    (net (code "10") (name "/SYNC4") (class "Default")
      (node (ref "U4") (pin "13") (pinfunction "SYNC#_13") (pintype "passive"))
    )
    (net (code "11") (name "/VREF1") (class "Default")
      (node (ref "C54") (pin "1") (pinfunction "1_1") (pintype "passive"))
      (node (ref "U1") (pin "4") (pinfunction "VREFIN/VREFOUT_4") (pintype "passive"))
      (node (ref "U2") (pin "4") (pinfunction "VREFIN/VREFOUT_4") (pintype "passive"))
      (node (ref "U3") (pin "4") (pinfunction "VREFIN/VREFOUT_4") (pintype "passive"))
      (node (ref "U4") (pin "4") (pinfunction "VREFIN/VREFOUT_4") (pintype "passive"))
      (node (ref "U5") (pin "6") (pinfunction "VOUT_6") (pintype "passive"))
    )
    (net (code "12") (name "/XOUT") (class "Default")
      (node (ref "R12") (pin "1") (pinfunction "1_1") (pintype "passive"))
      (node (ref "R7") (pin "1") (pinfunction "1_1") (pintype "passive"))
      (node (ref "U1") (pin "7") (pinfunction "VOUT_7") (pintype "passive"))
    )
    (net (code "13") (name "/YOUT") (class "Default")
      (node (ref "R16") (pin "2") (pinfunction "2_2") (pintype "passive"))
      (node (ref "R21") (pin "2") (pinfunction "2_2") (pintype "passive"))
      (node (ref "U2") (pin "7") (pinfunction "VOUT_7") (pintype "passive"))
    )
    (net (code "14") (name "/Z+X") (class "Default")
      (node (ref "R6") (pin "2") (pinfunction "2_2") (pintype "passive"))
    )
    (net (code "15") (name "/Z+Y") (class "Default")
      (node (ref "R14") (pin "1") (pinfunction "1_1") (pintype "passive"))
    )
    (net (code "16") (name "/Z-X") (class "Default")
      (node (ref "R9") (pin "2") (pinfunction "2_2") (pintype "passive"))
    )
    (net (code "17") (name "/Z-Y") (class "Default")
      (node (ref "R19") (pin "1") (pinfunction "1_1") (pintype "passive"))
    )
    (net (code "18") (name "/ZOUT") (class "Default")
      (node (ref "R13") (pin "1") (pinfunction "1_1") (pintype "passive"))
      (node (ref "R17") (pin "2") (pinfunction "2_2") (pintype "passive"))
      (node (ref "R22") (pin "2") (pinfunction "2_2") (pintype "passive"))
      (node (ref "R8") (pin "1") (pinfunction "1_1") (pintype "passive"))
      (node (ref "U3") (pin "7") (pinfunction "VOUT_7") (pintype "passive"))
    )
    (net (code "19") (name "3.3V") (class "Default")
      (node (ref "C11") (pin "1") (pinfunction "1_1") (pintype "passive"))
      (node (ref "C12") (pin "1") (pinfunction "1_1") (pintype "passive"))
      (node (ref "C17") (pin "1") (pinfunction "1_1") (pintype "passive"))
      (node (ref "C18") (pin "1") (pinfunction "1_1") (pintype "passive"))
      (node (ref "C23") (pin "1") (pinfunction "1_1") (pintype "passive"))
      (node (ref "C24") (pin "1") (pinfunction "1_1") (pintype "passive"))
      (node (ref "C5") (pin "1") (pinfunction "1_1") (pintype "passive"))
      (node (ref "C6") (pin "1") (pinfunction "1_1") (pintype "passive"))
      (node (ref "R1") (pin "1") (pinfunction "1_1") (pintype "passive"))
      (node (ref "R2") (pin "1") (pinfunction "1_1") (pintype "passive"))
      (node (ref "R3") (pin "1") (pinfunction "1_1") (pintype "passive"))
      (node (ref "R4") (pin "1") (pinfunction "1_1") (pintype "passive"))
      (node (ref "U1") (pin "15") (pinfunction "DVCC_15") (pintype "passive"))
      (node (ref "U2") (pin "15") (pinfunction "DVCC_15") (pintype "passive"))
      (node (ref "U3") (pin "15") (pinfunction "DVCC_15") (pintype "passive"))
      (node (ref "U4") (pin "15") (pinfunction "DVCC_15") (pintype "passive"))
    )
    (net (code "20") (name "AGND") (class "Default")
      (node (ref "C1") (pin "2") (pinfunction "2_2") (pintype "passive"))
      (node (ref "C10") (pin "1") (pinfunction "1_1") (pintype "passive"))
      (node (ref "C11") (pin "2") (pinfunction "2_2") (pintype "passive"))
      (node (ref "C12") (pin "2") (pinfunction "2_2") (pintype "passive"))
      (node (ref "C13") (pin "2") (pinfunction "2_2") (pintype "passive"))
      (node (ref "C14") (pin "2") (pinfunction "2_2") (pintype "passive"))
      (node (ref "C15") (pin "1") (pinfunction "1_1") (pintype "passive"))
      (node (ref "C16") (pin "1") (pinfunction "1_1") (pintype "passive"))
      (node (ref "C17") (pin "2") (pinfunction "2_2") (pintype "passive"))
      (node (ref "C18") (pin "2") (pinfunction "2_2") (pintype "passive"))
      (node (ref "C19") (pin "2") (pinfunction "2_2") (pintype "passive"))
      (node (ref "C2") (pin "2") (pinfunction "2_2") (pintype "passive"))
      (node (ref "C20") (pin "2") (pinfunction "2_2") (pintype "passive"))
      (node (ref "C21") (pin "1") (pinfunction "1_1") (pintype "passive"))
      (node (ref "C22") (pin "1") (pinfunction "1_1") (pintype "passive"))
      (node (ref "C23") (pin "2") (pinfunction "2_2") (pintype "passive"))
      (node (ref "C24") (pin "2") (pinfunction "2_2") (pintype "passive"))
      (node (ref "C25") (pin "1") (pinfunction "1_1") (pintype "passive"))
      (node (ref "C26") (pin "1") (pinfunction "1_1") (pintype "passive"))
      (node (ref "C3") (pin "1") (pinfunction "1_1") (pintype "passive"))
      (node (ref "C34") (pin "2") (pinfunction "2_2") (pintype "passive"))
      (node (ref "C35") (pin "1") (pinfunction "1_1") (pintype "passive"))
      (node (ref "C39") (pin "1") (pinfunction "1_1") (pintype "passive"))
      (node (ref "C4") (pin "1") (pinfunction "1_1") (pintype "passive"))
      (node (ref "C42") (pin "2") (pinfunction "2_2") (pintype "passive"))
      (node (ref "C43") (pin "1") (pinfunction "1_1") (pintype "passive"))
      (node (ref "C44") (pin "2") (pinfunction "2_2") (pintype "passive"))
      (node (ref "C45") (pin "2") (pinfunction "2_2") (pintype "passive"))
      (node (ref "C46") (pin "1") (pinfunction "1_1") (pintype "passive"))
      (node (ref "C5") (pin "2") (pinfunction "2_2") (pintype "passive"))
      (node (ref "C54") (pin "2") (pinfunction "2_2") (pintype "passive"))
      (node (ref "C6") (pin "2") (pinfunction "2_2") (pintype "passive"))
      (node (ref "C7") (pin "2") (pinfunction "2_2") (pintype "passive"))
      (node (ref "C8") (pin "2") (pinfunction "2_2") (pintype "passive"))
      (node (ref "C9") (pin "1") (pinfunction "1_1") (pintype "passive"))
      (node (ref "R11") (pin "1") (pinfunction "1_1") (pintype "passive"))
      (node (ref "R20") (pin "2") (pinfunction "2_2") (pintype "passive"))
      (node (ref "U1") (pin "16") (pinfunction "DGND_16") (pintype "passive"))
      (node (ref "U1") (pin "5") (pinfunction "AGND_5") (pintype "passive"))
      (node (ref "U10") (pin "5") (pinfunction "IN_B+_5") (pintype "passive"))
      (node (ref "U13") (pin "3") (pinfunction "INA+_3") (pintype "passive"))
      (node (ref "U2") (pin "16") (pinfunction "DGND_16") (pintype "passive"))
      (node (ref "U2") (pin "5") (pinfunction "AGND_5") (pintype "passive"))
      (node (ref "U3") (pin "16") (pinfunction "DGND_16") (pintype "passive"))
      (node (ref "U3") (pin "5") (pinfunction "AGND_5") (pintype "passive"))
      (node (ref "U4") (pin "16") (pinfunction "DGND_16") (pintype "passive"))
      (node (ref "U4") (pin "5") (pinfunction "AGND_5") (pintype "passive"))
      (node (ref "U5") (pin "4") (pinfunction "GND_4") (pintype "passive"))
      (node (ref "U9") (pin "5") (pinfunction "IN_B+_5") (pintype "passive"))
    )
    (net (code "21") (name "Net-(LED1-A)") (class "Default")
      (node (ref "LED1") (pin "1") (pinfunction "A_1") (pintype "passive"))
      (node (ref "R1") (pin "2") (pinfunction "2_2") (pintype "passive"))
    )
    (net (code "22") (name "Net-(LED1-C)") (class "Default")
      (node (ref "LED1") (pin "2") (pinfunction "C_2") (pintype "passive"))
      (node (ref "U1") (pin "1") (pinfunction "ALERT#_1") (pintype "passive"))
    )
    (net (code "23") (name "Net-(LED2-A)") (class "Default")
      (node (ref "LED2") (pin "1") (pinfunction "A_1") (pintype "passive"))
      (node (ref "R2") (pin "2") (pinfunction "2_2") (pintype "passive"))
    )
    (net (code "24") (name "Net-(LED2-C)") (class "Default")
      (node (ref "LED2") (pin "2") (pinfunction "C_2") (pintype "passive"))
      (node (ref "U2") (pin "1") (pinfunction "ALERT#_1") (pintype "passive"))
    )
    (net (code "25") (name "Net-(LED3-A)") (class "Default")
      (node (ref "LED3") (pin "1") (pinfunction "A_1") (pintype "passive"))
      (node (ref "R3") (pin "2") (pinfunction "2_2") (pintype "passive"))
    )
    (net (code "26") (name "Net-(LED3-C)") (class "Default")
      (node (ref "LED3") (pin "2") (pinfunction "C_2") (pintype "passive"))
      (node (ref "U3") (pin "1") (pinfunction "ALERT#_1") (pintype "passive"))
    )
    (net (code "27") (name "Net-(LED4-A)") (class "Default")
      (node (ref "LED4") (pin "1") (pinfunction "A_1") (pintype "passive"))
      (node (ref "R4") (pin "2") (pinfunction "2_2") (pintype "passive"))
    )
    (net (code "28") (name "Net-(LED4-C)") (class "Default")
      (node (ref "LED4") (pin "2") (pinfunction "C_2") (pintype "passive"))
      (node (ref "U4") (pin "1") (pinfunction "ALERT#_1") (pintype "passive"))
    )
    (net (code "29") (name "Net-(U9A-IN_B-)") (class "Default")
      (node (ref "C37") (pin "1") (pinfunction "1_1") (pintype "passive"))
      (node (ref "R5") (pin "1") (pinfunction "1_1") (pintype "passive"))
      (node (ref "R7") (pin "2") (pinfunction "2_2") (pintype "passive"))
      (node (ref "R8") (pin "2") (pinfunction "2_2") (pintype "passive"))
      (node (ref "U9") (pin "6") (pinfunction "IN_B-_6") (pintype "passive"))
    )
    (net (code "30") (name "Net-(U9A-OUT_B)") (class "Default")
      (node (ref "C37") (pin "2") (pinfunction "2_2") (pintype "passive"))
      (node (ref "R5") (pin "2") (pinfunction "2_2") (pintype "passive"))
      (node (ref "R6") (pin "1") (pinfunction "1_1") (pintype "passive"))
      (node (ref "U9") (pin "7") (pinfunction "OUT_B_7") (pintype "passive"))
    )
    (net (code "31") (name "Net-(U9B-IN_A+)") (class "Default")
      (node (ref "C39") (pin "2") (pinfunction "2_2") (pintype "passive"))
      (node (ref "R11") (pin "2") (pinfunction "2_2") (pintype "passive"))
      (node (ref "R12") (pin "2") (pinfunction "2_2") (pintype "passive"))
      (node (ref "U9") (pin "3") (pinfunction "IN_A+_3") (pintype "passive"))
    )
    (net (code "32") (name "Net-(U9B-IN_A-)") (class "Default")
      (node (ref "C38") (pin "1") (pinfunction "1_1") (pintype "passive"))
      (node (ref "R10") (pin "1") (pinfunction "1_1") (pintype "passive"))
      (node (ref "R13") (pin "2") (pinfunction "2_2") (pintype "passive"))
      (node (ref "U9") (pin "2") (pinfunction "IN_A-_2") (pintype "passive"))
    )
    (net (code "33") (name "Net-(U9B-OUT_A)") (class "Default")
      (node (ref "C38") (pin "2") (pinfunction "2_2") (pintype "passive"))
      (node (ref "R10") (pin "2") (pinfunction "2_2") (pintype "passive"))
      (node (ref "R9") (pin "1") (pinfunction "1_1") (pintype "passive"))
      (node (ref "U9") (pin "1") (pinfunction "OUT_A_1") (pintype "passive"))
    )
    (net (code "34") (name "Net-(U10A-IN_B-)") (class "Default")
      (node (ref "C40") (pin "2") (pinfunction "2_2") (pintype "passive"))
      (node (ref "R15") (pin "2") (pinfunction "2_2") (pintype "passive"))
      (node (ref "R16") (pin "1") (pinfunction "1_1") (pintype "passive"))
      (node (ref "R17") (pin "1") (pinfunction "1_1") (pintype "passive"))
      (node (ref "U10") (pin "6") (pinfunction "IN_B-_6") (pintype "passive"))
    )
    (net (code "35") (name "Net-(U10A-OUT_B)") (class "Default")
      (node (ref "C40") (pin "1") (pinfunction "1_1") (pintype "passive"))
      (node (ref "R14") (pin "2") (pinfunction "2_2") (pintype "passive"))
      (node (ref "R15") (pin "1") (pinfunction "1_1") (pintype "passive"))
      (node (ref "U10") (pin "7") (pinfunction "OUT_B_7") (pintype "passive"))
    )
    (net (code "36") (name "Net-(U10B-IN_A+)") (class "Default")
      (node (ref "C42") (pin "1") (pinfunction "1_1") (pintype "passive"))
      (node (ref "R20") (pin "1") (pinfunction "1_1") (pintype "passive"))
      (node (ref "R21") (pin "1") (pinfunction "1_1") (pintype "passive"))
      (node (ref "U10") (pin "3") (pinfunction "IN_A+_3") (pintype "passive"))
    )
    (net (code "37") (name "Net-(U10B-IN_A-)") (class "Default")
      (node (ref "C41") (pin "2") (pinfunction "2_2") (pintype "passive"))
      (node (ref "R18") (pin "2") (pinfunction "2_2") (pintype "passive"))
      (node (ref "R22") (pin "1") (pinfunction "1_1") (pintype "passive"))
      (node (ref "U10") (pin "2") (pinfunction "IN_A-_2") (pintype "passive"))
    )
    (net (code "38") (name "Net-(U10B-OUT_A)") (class "Default")
      (node (ref "C41") (pin "1") (pinfunction "1_1") (pintype "passive"))
      (node (ref "R18") (pin "1") (pinfunction "1_1") (pintype "passive"))
      (node (ref "R19") (pin "2") (pinfunction "2_2") (pintype "passive"))
      (node (ref "U10") (pin "1") (pinfunction "OUT_A_1") (pintype "passive"))
    )
    (net (code "39") (name "Net-(U13A-INA-)") (class "Default")
      (node (ref "C48") (pin "1") (pinfunction "1_1") (pintype "passive"))
      (node (ref "R30") (pin "2") (pinfunction "2_2") (pintype "passive"))
      (node (ref "R31") (pin "1") (pinfunction "1_1") (pintype "passive"))
      (node (ref "U13") (pin "2") (pinfunction "INA-_2") (pintype "passive"))
    )
    (net (code "40") (name "Net-(U13A-OUTA)") (class "Default")
      (node (ref "C48") (pin "2") (pinfunction "2_2") (pintype "passive"))
      (node (ref "R31") (pin "2") (pinfunction "2_2") (pintype "passive"))
      (node (ref "R32") (pin "1") (pinfunction "1_1") (pintype "passive"))
      (node (ref "U13") (pin "1") (pinfunction "OUTA_1") (pintype "passive"))
    )
    (net (code "41") (name "unconnected-(U1-CLEAR#-Pad2)") (class "Default")
      (node (ref "U1") (pin "2") (pinfunction "CLEAR#_2") (pintype "passive+no_connect"))
    )
    (net (code "42") (name "unconnected-(U1-DNC-Pad9)") (class "Default")
      (node (ref "U1") (pin "9") (pinfunction "DNC_9") (pintype "passive+no_connect"))
    )
    (net (code "43") (name "unconnected-(U1-LDAC#-Pad11)") (class "Default")
      (node (ref "U1") (pin "11") (pinfunction "LDAC#_11") (pintype "passive+no_connect"))
    )
    (net (code "44") (name "unconnected-(U1-RESET#-Pad3)") (class "Default")
      (node (ref "U1") (pin "3") (pinfunction "RESET#_3") (pintype "passive+no_connect"))
    )
    (net (code "45") (name "unconnected-(U1-SDO-Pad10)") (class "Default")
      (node (ref "U1") (pin "10") (pinfunction "SDO_10") (pintype "passive+no_connect"))
    )
    (net (code "46") (name "unconnected-(U2-CLEAR#-Pad2)") (class "Default")
      (node (ref "U2") (pin "2") (pinfunction "CLEAR#_2") (pintype "passive+no_connect"))
    )
    (net (code "47") (name "unconnected-(U2-DNC-Pad9)") (class "Default")
      (node (ref "U2") (pin "9") (pinfunction "DNC_9") (pintype "passive+no_connect"))
    )
    (net (code "48") (name "unconnected-(U2-LDAC#-Pad11)") (class "Default")
      (node (ref "U2") (pin "11") (pinfunction "LDAC#_11") (pintype "passive+no_connect"))
    )
    (net (code "49") (name "unconnected-(U2-RESET#-Pad3)") (class "Default")
      (node (ref "U2") (pin "3") (pinfunction "RESET#_3") (pintype "passive+no_connect"))
    )
    (net (code "50") (name "unconnected-(U2-SDO-Pad10)") (class "Default")
      (node (ref "U2") (pin "10") (pinfunction "SDO_10") (pintype "passive+no_connect"))
    )
    (net (code "51") (name "unconnected-(U3-CLEAR#-Pad2)") (class "Default")
      (node (ref "U3") (pin "2") (pinfunction "CLEAR#_2") (pintype "passive+no_connect"))
    )
    (net (code "52") (name "unconnected-(U3-DNC-Pad9)") (class "Default")
      (node (ref "U3") (pin "9") (pinfunction "DNC_9") (pintype "passive+no_connect"))
    )
    (net (code "53") (name "unconnected-(U3-LDAC#-Pad11)") (class "Default")
      (node (ref "U3") (pin "11") (pinfunction "LDAC#_11") (pintype "passive+no_connect"))
    )
    (net (code "54") (name "unconnected-(U3-RESET#-Pad3)") (class "Default")
      (node (ref "U3") (pin "3") (pinfunction "RESET#_3") (pintype "passive+no_connect"))
    )
    (net (code "55") (name "unconnected-(U3-SDO-Pad10)") (class "Default")
      (node (ref "U3") (pin "10") (pinfunction "SDO_10") (pintype "passive+no_connect"))
    )
    (net (code "56") (name "unconnected-(U4-CLEAR#-Pad2)") (class "Default")
      (node (ref "U4") (pin "2") (pinfunction "CLEAR#_2") (pintype "passive+no_connect"))
    )
    (net (code "57") (name "unconnected-(U4-DNC-Pad9)") (class "Default")
      (node (ref "U4") (pin "9") (pinfunction "DNC_9") (pintype "passive+no_connect"))
    )
    (net (code "58") (name "unconnected-(U4-LDAC#-Pad11)") (class "Default")
      (node (ref "U4") (pin "11") (pinfunction "LDAC#_11") (pintype "passive+no_connect"))
    )
    (net (code "59") (name "unconnected-(U4-RESET#-Pad3)") (class "Default")
      (node (ref "U4") (pin "3") (pinfunction "RESET#_3") (pintype "passive+no_connect"))
    )
    (net (code "60") (name "unconnected-(U4-SDO-Pad10)") (class "Default")
      (node (ref "U4") (pin "10") (pinfunction "SDO_10") (pintype "passive+no_connect"))
    )
    (net (code "61") (name "unconnected-(U5-NIC-Pad3)") (class "Default")
      (node (ref "U5") (pin "3") (pinfunction "NIC_3") (pintype "passive+no_connect"))
    )
    (net (code "62") (name "unconnected-(U5-NIC-Pad7)") (class "Default")
      (node (ref "U5") (pin "7") (pinfunction "NIC_7") (pintype "passive+no_connect"))
    )
    (net (code "63") (name "unconnected-(U5-TP-Pad1)") (class "Default")
      (node (ref "U5") (pin "1") (pinfunction "TP_1") (pintype "passive+no_connect"))
    )
    (net (code "64") (name "unconnected-(U5-TP-Pad8)") (class "Default")
      (node (ref "U5") (pin "8") (pinfunction "TP_8") (pintype "passive+no_connect"))
    )
    (net (code "65") (name "unconnected-(U5-TRIM-Pad5)") (class "Default")
      (node (ref "U5") (pin "5") (pinfunction "TRIM_5") (pintype "passive+no_connect"))
    )
  )
)
